# 1-Schematic__Error.net
KiCad netlist of a schematic drawn in EasyEDA
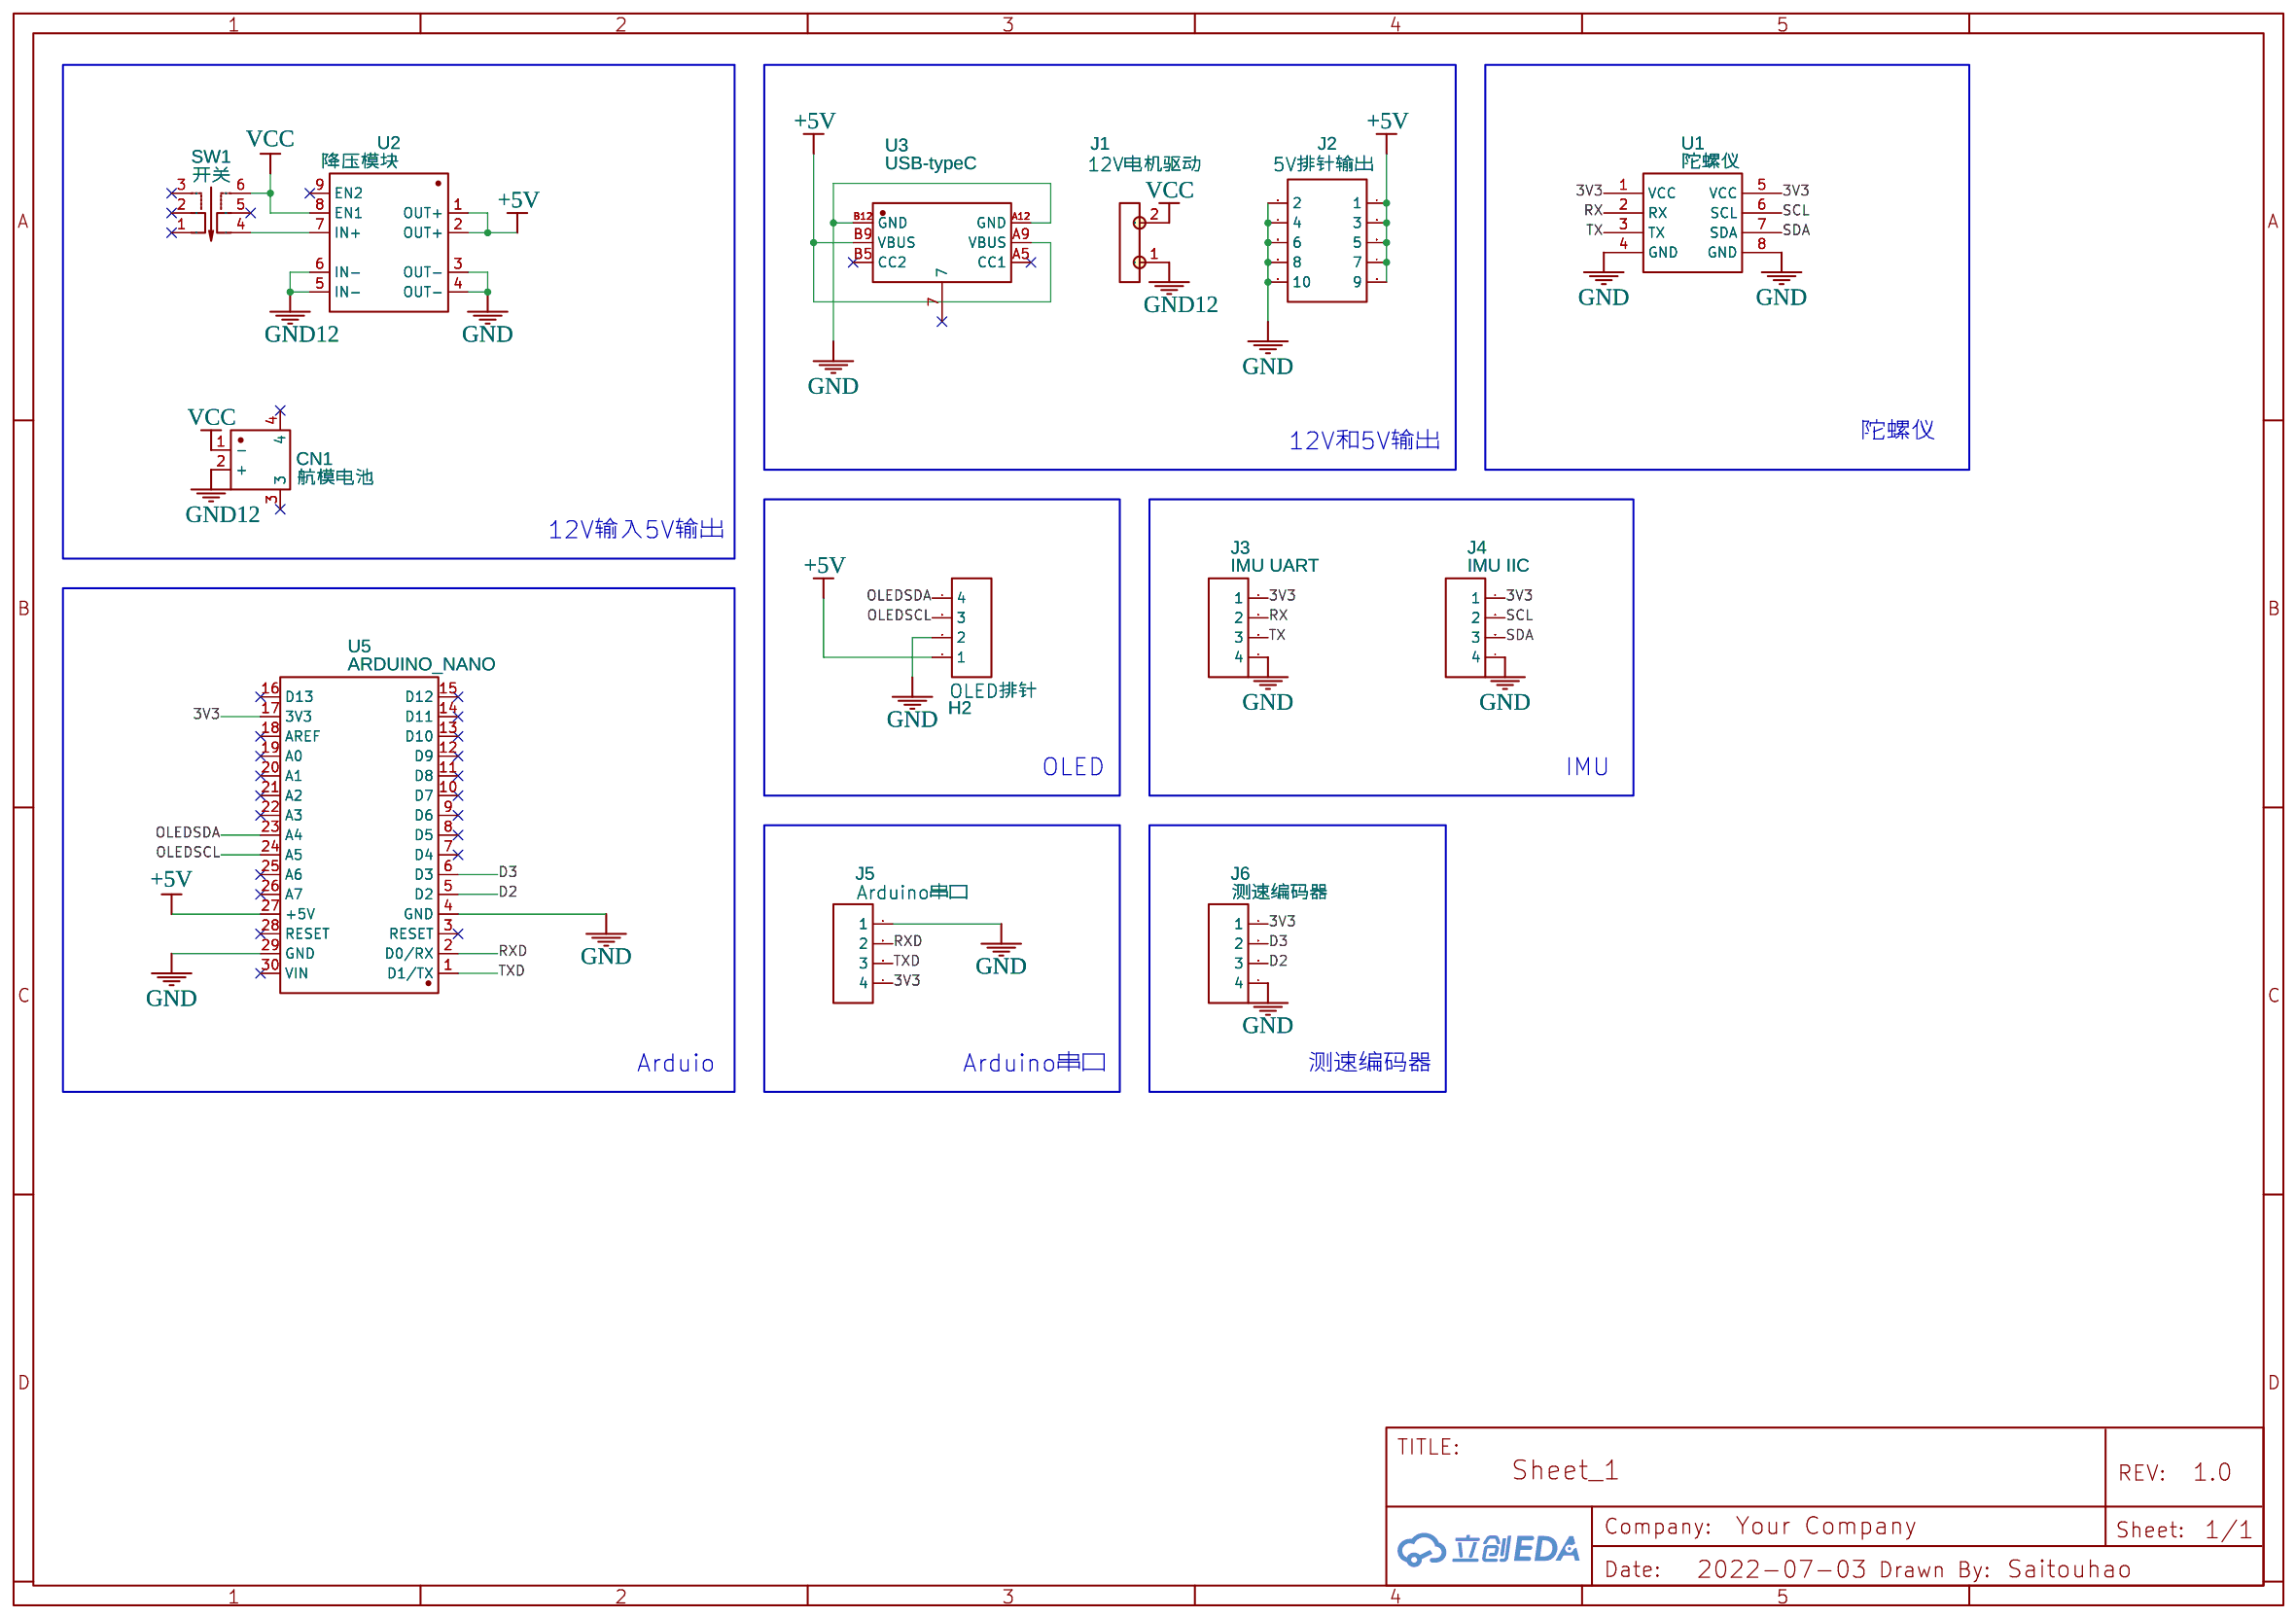
[diagram p0: schematic sheet]

(export (version "E")
  (design (tool "Eeschema 10.0.6"))
  (components
    (comp (ref "CN1")
      (value "航模电池")
      (fields (field (name "BOM_Manufacturer Part") "XT60PW-M") (field (name "BOM_Supplier Part") "C98732"))
      (libsource (lib "") (part "XT60PW-M"))
    )
    (comp (ref "H2")
      (value "OLED排针")
      (fields (field (name "BOM_Supplier Part") "C225501"))
      (libsource (lib "") (part "HDR-F-2.54_1x4"))
    )
    (comp (ref "J1") (value "12V电机驱动") (libsource (lib "") (part "CON1X02")))
    (comp (ref "J2")
      (value "5V排针输出")
      (fields (field (name "BOM_Supplier Part") "C178292"))
      (libsource (lib "") (part "HDR-M-2.54_2x5"))
    )
    (comp (ref "J3")
      (value "IMU UART")
      (fields (field (name "BOM_Supplier Part") "C124378"))
      (libsource (lib "") (part "HDR-M-2.54_1x4"))
    )
    (comp (ref "J4")
      (value "IMU IIC")
      (fields (field (name "BOM_Supplier Part") "C124378"))
      (libsource (lib "") (part "HDR-M-2.54_1x4"))
    )
    (comp (ref "J5")
      (value "Arduino串口")
      (fields (field (name "BOM_Supplier Part") "C124378"))
      (libsource (lib "") (part "HDR-M-2.54_1x4"))
    )
    (comp (ref "J6")
      (value "测速编码器")
      (fields (field (name "BOM_Supplier Part") "C124378"))
      (libsource (lib "") (part "HDR-M-2.54_1x4"))
    )
    (comp (ref "SW1")
      (value "开关")
      (fields (field (name "BOM_Manufacturer Part") "PB22E60L") (field (name "BOM_Supplier Part") "C2987421"))
      (libsource (lib "") (part "PB22E60L"))
    )
    (comp (ref "U1") (value "陀螺仪") (libsource (lib "") (part "JY61-DIP8")))
    (comp (ref "U2") (value "降压模块") (libsource (lib "") (part "XN-50L")))
    (comp (ref "U3")
      (value "USB-typeC")
      (fields
        (field (name "BOM_Manufacturer Part") "USB-TYPE-C6P")
        (field (name "BOM_Supplier Part") "C9900001831")
      )
      (libsource (lib "") (part "USB-TYPE-C6P"))
    )
    (comp (ref "U5")
      (value "ARDUINO_NANO")
      (fields (field (name "BOM_Supplier Part") "C9900017879"))
      (libsource (lib "") (part "ARDUINO_NANO"))
    )
  )
  (nets
    (net (code "1") (name "+5V") (class "Default")
      (node (ref "H2") (pin "1") (pinfunction "1_1") (pintype "unspecified"))
      (node (ref "J2") (pin "1") (pinfunction "1_1") (pintype "unspecified"))
      (node (ref "J2") (pin "3") (pinfunction "3_3") (pintype "unspecified"))
      (node (ref "J2") (pin "5") (pinfunction "5_5") (pintype "unspecified"))
      (node (ref "J2") (pin "7") (pinfunction "7_7") (pintype "unspecified"))
      (node (ref "J2") (pin "9") (pinfunction "9_9") (pintype "unspecified"))
      (node (ref "U2") (pin "1") (pinfunction "OUT+_1") (pintype "unspecified"))
      (node (ref "U2") (pin "2") (pinfunction "OUT+_2") (pintype "unspecified"))
      (node (ref "U3") (pin "A9") (pinfunction "VBUS_A9") (pintype "unspecified"))
      (node (ref "U3") (pin "B9") (pinfunction "VBUS_B9") (pintype "unspecified"))
      (node (ref "U5") (pin "27") (pinfunction "+5V_27") (pintype "unspecified"))
    )
    (net (code "2") (name "/3V3") (class "Default")
      (node (ref "J3") (pin "1") (pinfunction "1_1") (pintype "unspecified"))
      (node (ref "J4") (pin "1") (pinfunction "1_1") (pintype "unspecified"))
      (node (ref "J5") (pin "4") (pinfunction "4_4") (pintype "unspecified"))
      (node (ref "J6") (pin "1") (pinfunction "1_1") (pintype "unspecified"))
      (node (ref "U1") (pin "1") (pinfunction "VCC_1") (pintype "unspecified"))
      (node (ref "U1") (pin "5") (pinfunction "VCC_5") (pintype "unspecified"))
      (node (ref "U5") (pin "17") (pinfunction "3V3_17") (pintype "unspecified"))
    )
    (net (code "3") (name "/D2") (class "Default")
      (node (ref "J6") (pin "3") (pinfunction "3_3") (pintype "unspecified"))
      (node (ref "U5") (pin "5") (pinfunction "D2_5") (pintype "unspecified"))
    )
    (net (code "4") (name "/D3") (class "Default")
      (node (ref "J6") (pin "2") (pinfunction "2_2") (pintype "unspecified"))
      (node (ref "U5") (pin "6") (pinfunction "D3_6") (pintype "unspecified"))
    )
    (net (code "5") (name "/OLEDSCL") (class "Default")
      (node (ref "H2") (pin "3") (pinfunction "3_3") (pintype "unspecified"))
      (node (ref "U5") (pin "24") (pinfunction "A5_24") (pintype "unspecified"))
    )
    (net (code "6") (name "/OLEDSDA") (class "Default")
      (node (ref "H2") (pin "4") (pinfunction "4_4") (pintype "unspecified"))
      (node (ref "U5") (pin "23") (pinfunction "A4_23") (pintype "unspecified"))
    )
    (net (code "7") (name "/RX") (class "Default")
      (node (ref "J3") (pin "2") (pinfunction "2_2") (pintype "unspecified"))
      (node (ref "U1") (pin "2") (pinfunction "RX_2") (pintype "unspecified"))
    )
    (net (code "8") (name "/RXD") (class "Default")
      (node (ref "J5") (pin "2") (pinfunction "2_2") (pintype "unspecified"))
      (node (ref "U5") (pin "2") (pinfunction "D0/RX_2") (pintype "unspecified"))
    )
    (net (code "9") (name "/SCL") (class "Default")
      (node (ref "J4") (pin "2") (pinfunction "2_2") (pintype "unspecified"))
      (node (ref "U1") (pin "6") (pinfunction "SCL_6") (pintype "unspecified"))
    )
    (net (code "10") (name "/SDA") (class "Default")
      (node (ref "J4") (pin "3") (pinfunction "3_3") (pintype "unspecified"))
      (node (ref "U1") (pin "7") (pinfunction "SDA_7") (pintype "unspecified"))
    )
    (net (code "11") (name "/TX") (class "Default")
      (node (ref "J3") (pin "3") (pinfunction "3_3") (pintype "unspecified"))
      (node (ref "U1") (pin "3") (pinfunction "TX_3") (pintype "unspecified"))
    )
    (net (code "12") (name "/TXD") (class "Default")
      (node (ref "J5") (pin "3") (pinfunction "3_3") (pintype "unspecified"))
      (node (ref "U5") (pin "1") (pinfunction "D1/TX_1") (pintype "unspecified"))
    )
    (net (code "13") (name "GND") (class "Default")
      (node (ref "H2") (pin "2") (pinfunction "2_2") (pintype "unspecified"))
      (node (ref "J2") (pin "10") (pinfunction "10_10") (pintype "unspecified"))
      (node (ref "J2") (pin "2") (pinfunction "2_2") (pintype "unspecified"))
      (node (ref "J2") (pin "4") (pinfunction "4_4") (pintype "unspecified"))
      (node (ref "J2") (pin "6") (pinfunction "6_6") (pintype "unspecified"))
      (node (ref "J2") (pin "8") (pinfunction "8_8") (pintype "unspecified"))
      (node (ref "J3") (pin "4") (pinfunction "4_4") (pintype "unspecified"))
      (node (ref "J4") (pin "4") (pinfunction "4_4") (pintype "unspecified"))
      (node (ref "J5") (pin "1") (pinfunction "1_1") (pintype "unspecified"))
      (node (ref "J6") (pin "4") (pinfunction "4_4") (pintype "unspecified"))
      (node (ref "U1") (pin "4") (pinfunction "GND_4") (pintype "unspecified"))
      (node (ref "U1") (pin "8") (pinfunction "GND_8") (pintype "unspecified"))
      (node (ref "U2") (pin "3") (pinfunction "OUT-_3") (pintype "unspecified"))
      (node (ref "U2") (pin "4") (pinfunction "OUT-_4") (pintype "unspecified"))
      (node (ref "U3") (pin "A12") (pinfunction "GND_A12") (pintype "unspecified"))
      (node (ref "U3") (pin "B12") (pinfunction "GND_B12") (pintype "unspecified"))
      (node (ref "U5") (pin "29") (pinfunction "GND_29") (pintype "unspecified"))
      (node (ref "U5") (pin "4") (pinfunction "GND_4") (pintype "unspecified"))
    )
    (net (code "14") (name "GND12") (class "Default")
      (node (ref "CN1") (pin "2") (pinfunction "+_2") (pintype "unspecified"))
      (node (ref "J1") (pin "1") (pinfunction "1_1") (pintype "unspecified"))
      (node (ref "U2") (pin "5") (pinfunction "IN-_5") (pintype "unspecified"))
      (node (ref "U2") (pin "6") (pinfunction "IN-_6") (pintype "unspecified"))
    )
    (net (code "15") (name "Net-(U2-IN+)") (class "Default")
      (node (ref "SW1") (pin "4") (pinfunction "4_4") (pintype "unspecified"))
      (node (ref "U2") (pin "7") (pinfunction "IN+_7") (pintype "unspecified"))
    )
    (net (code "16") (name "VCC") (class "Default")
      (node (ref "CN1") (pin "1") (pinfunction "-_1") (pintype "unspecified"))
      (node (ref "J1") (pin "2") (pinfunction "2_2") (pintype "unspecified"))
      (node (ref "SW1") (pin "6") (pinfunction "6_6") (pintype "unspecified"))
      (node (ref "U2") (pin "8") (pinfunction "EN1_8") (pintype "unspecified"))
    )
    (net (code "17") (name "unconnected-(CN1-Pad3)") (class "Default")
      (node (ref "CN1") (pin "3") (pinfunction "3_3") (pintype "unspecified+no_connect"))
    )
    (net (code "18") (name "unconnected-(CN1-Pad4)") (class "Default")
      (node (ref "CN1") (pin "4") (pinfunction "4_4") (pintype "unspecified+no_connect"))
    )
    (net (code "19") (name "unconnected-(SW1-Pad1)") (class "Default")
      (node (ref "SW1") (pin "1") (pinfunction "1_1") (pintype "unspecified+no_connect"))
    )
    (net (code "20") (name "unconnected-(SW1-Pad2)") (class "Default")
      (node (ref "SW1") (pin "2") (pinfunction "2_2") (pintype "unspecified+no_connect"))
    )
    (net (code "21") (name "unconnected-(SW1-Pad3)") (class "Default")
      (node (ref "SW1") (pin "3") (pinfunction "3_3") (pintype "unspecified+no_connect"))
    )
    (net (code "22") (name "unconnected-(SW1-Pad5)") (class "Default")
      (node (ref "SW1") (pin "5") (pinfunction "5_5") (pintype "unspecified+no_connect"))
    )
    (net (code "23") (name "unconnected-(U2-EN2-Pad9)") (class "Default")
      (node (ref "U2") (pin "9") (pinfunction "EN2_9") (pintype "unspecified+no_connect"))
    )
    (net (code "24") (name "unconnected-(U3-CC1-PadA5)") (class "Default")
      (node (ref "U3") (pin "A5") (pinfunction "CC1_A5") (pintype "unspecified+no_connect"))
    )
    (net (code "25") (name "unconnected-(U3-CC2-PadB5)") (class "Default")
      (node (ref "U3") (pin "B5") (pinfunction "CC2_B5") (pintype "unspecified+no_connect"))
    )
    (net (code "26") (name "unconnected-(U3-Pad7)") (class "Default")
      (node (ref "U3") (pin "7") (pinfunction "7_7") (pintype "unspecified+no_connect"))
    )
    (net (code "27") (name "unconnected-(U5-A0-Pad19)") (class "Default")
      (node (ref "U5") (pin "19") (pinfunction "A0_19") (pintype "unspecified+no_connect"))
    )
    (net (code "28") (name "unconnected-(U5-A1-Pad20)") (class "Default")
      (node (ref "U5") (pin "20") (pinfunction "A1_20") (pintype "unspecified+no_connect"))
    )
    (net (code "29") (name "unconnected-(U5-A2-Pad21)") (class "Default")
      (node (ref "U5") (pin "21") (pinfunction "A2_21") (pintype "unspecified+no_connect"))
    )
    (net (code "30") (name "unconnected-(U5-A3-Pad22)") (class "Default")
      (node (ref "U5") (pin "22") (pinfunction "A3_22") (pintype "unspecified+no_connect"))
    )
    (net (code "31") (name "unconnected-(U5-A6-Pad25)") (class "Default")
      (node (ref "U5") (pin "25") (pinfunction "A6_25") (pintype "unspecified+no_connect"))
    )
    (net (code "32") (name "unconnected-(U5-A7-Pad26)") (class "Default")
      (node (ref "U5") (pin "26") (pinfunction "A7_26") (pintype "unspecified+no_connect"))
    )
    (net (code "33") (name "unconnected-(U5-AREF-Pad18)") (class "Default")
      (node (ref "U5") (pin "18") (pinfunction "AREF_18") (pintype "unspecified+no_connect"))
    )
    (net (code "34") (name "unconnected-(U5-D4-Pad7)") (class "Default")
      (node (ref "U5") (pin "7") (pinfunction "D4_7") (pintype "unspecified+no_connect"))
    )
    (net (code "35") (name "unconnected-(U5-D5-Pad8)") (class "Default")
      (node (ref "U5") (pin "8") (pinfunction "D5_8") (pintype "unspecified+no_connect"))
    )
    (net (code "36") (name "unconnected-(U5-D6-Pad9)") (class "Default")
      (node (ref "U5") (pin "9") (pinfunction "D6_9") (pintype "unspecified+no_connect"))
    )
    (net (code "37") (name "unconnected-(U5-D7-Pad10)") (class "Default")
      (node (ref "U5") (pin "10") (pinfunction "D7_10") (pintype "unspecified+no_connect"))
    )
    (net (code "38") (name "unconnected-(U5-D8-Pad11)") (class "Default")
      (node (ref "U5") (pin "11") (pinfunction "D8_11") (pintype "unspecified+no_connect"))
    )
    (net (code "39") (name "unconnected-(U5-D9-Pad12)") (class "Default")
      (node (ref "U5") (pin "12") (pinfunction "D9_12") (pintype "unspecified+no_connect"))
    )
    (net (code "40") (name "unconnected-(U5-D10-Pad13)") (class "Default")
      (node (ref "U5") (pin "13") (pinfunction "D10_13") (pintype "unspecified+no_connect"))
    )
    (net (code "41") (name "unconnected-(U5-D11-Pad14)") (class "Default")
      (node (ref "U5") (pin "14") (pinfunction "D11_14") (pintype "unspecified+no_connect"))
    )
    (net (code "42") (name "unconnected-(U5-D12-Pad15)") (class "Default")
      (node (ref "U5") (pin "15") (pinfunction "D12_15") (pintype "unspecified+no_connect"))
    )
    (net (code "43") (name "unconnected-(U5-D13-Pad16)") (class "Default")
      (node (ref "U5") (pin "16") (pinfunction "D13_16") (pintype "unspecified+no_connect"))
    )
    (net (code "44") (name "unconnected-(U5-RESET-Pad3)") (class "Default")
      (node (ref "U5") (pin "3") (pinfunction "RESET_3") (pintype "unspecified+no_connect"))
    )
    (net (code "45") (name "unconnected-(U5-RESET-Pad28)") (class "Default")
      (node (ref "U5") (pin "28") (pinfunction "RESET_28") (pintype "unspecified+no_connect"))
    )
    (net (code "46") (name "unconnected-(U5-VIN-Pad30)") (class "Default")
      (node (ref "U5") (pin "30") (pinfunction "VIN_30") (pintype "unspecified+no_connect"))
    )
  )
)
